# INTERFACE.net
KiCad netlist of a schematic drawn in Altium Designer
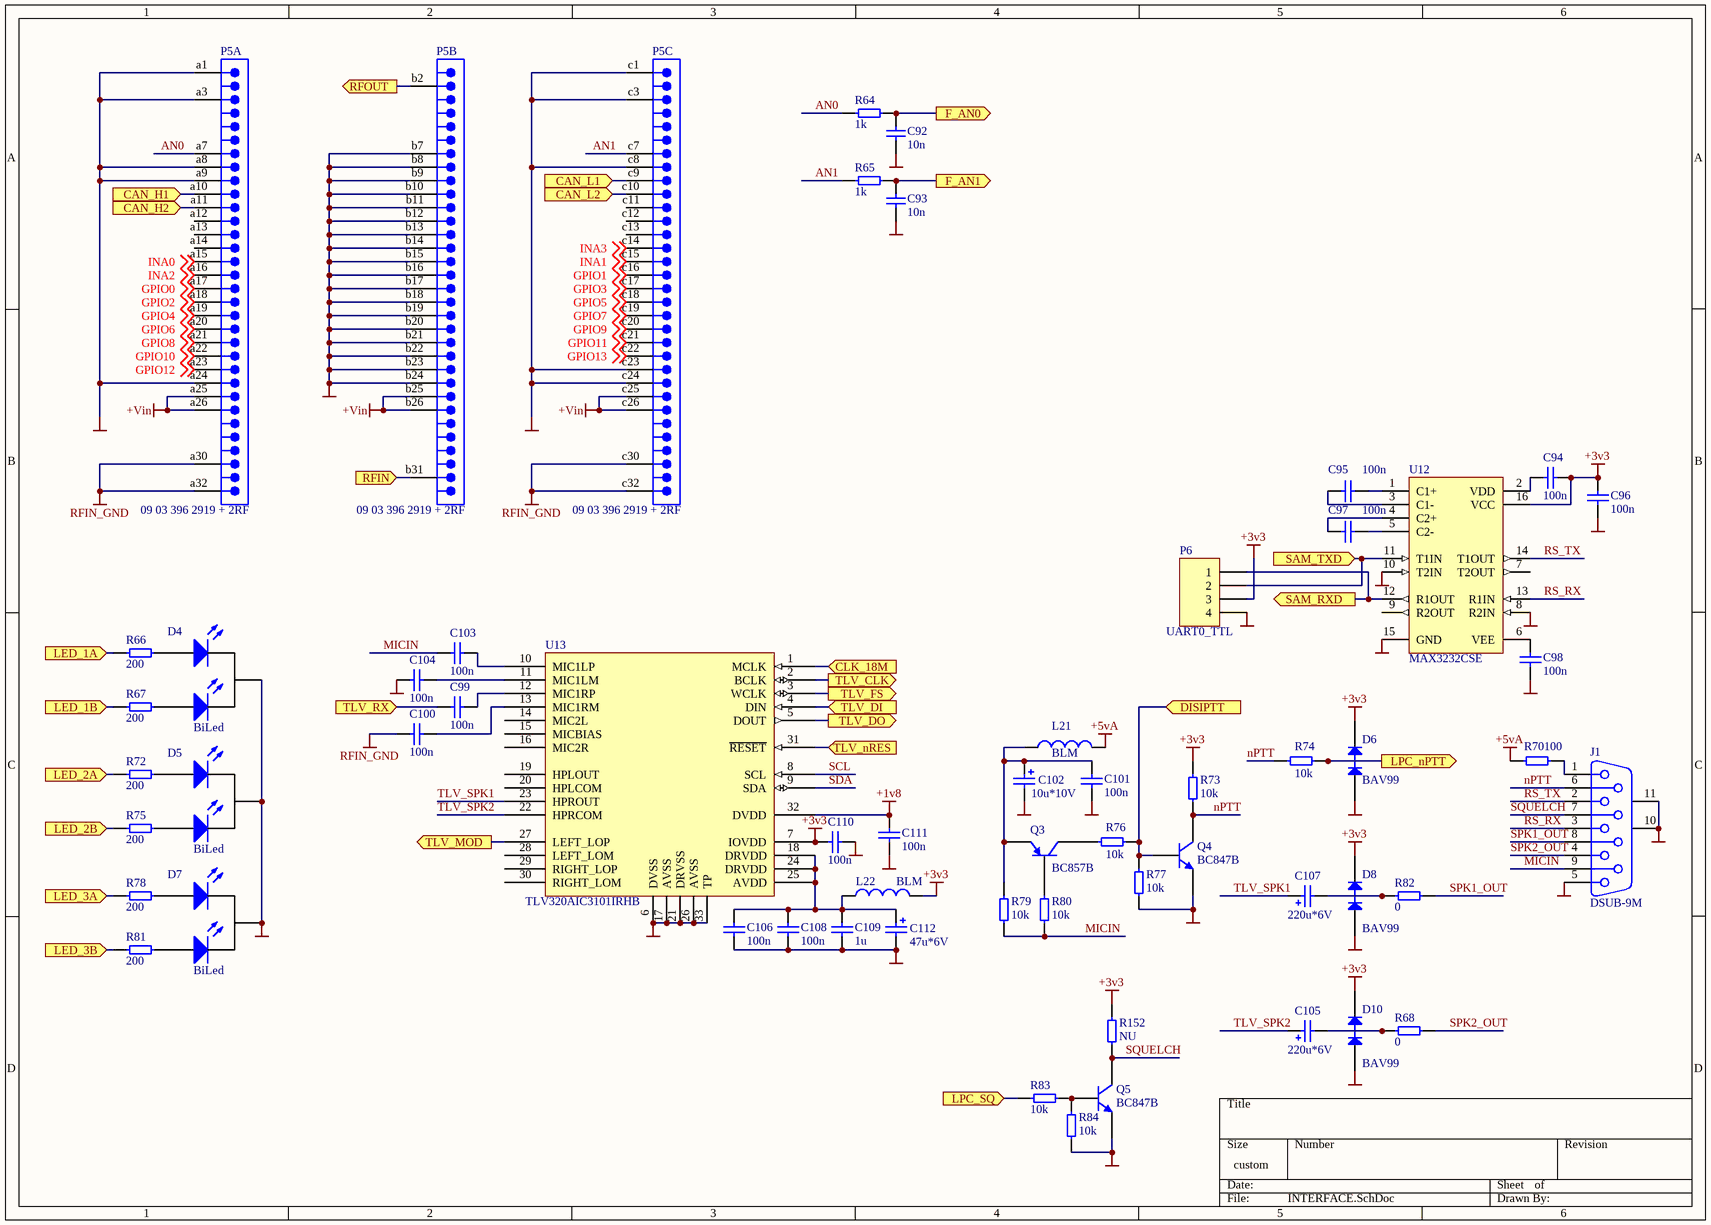
[diagram p0: INTERFACE.SchDoc]

(export (version "E")
  (design (tool "Eeschema 10.0.6"))
  (components
    (comp (ref "C92")
      (value "10n")
      (footprint "CAPC1608L")
      (description "Capacitor")
      (fields (field (name "PUBLISHER") "Altium Limited"))
      (libsource (lib "") (part "Cap_1"))
    )
    (comp (ref "C93")
      (value "10n")
      (footprint "CAPC1608L")
      (description "Capacitor")
      (fields (field (name "PUBLISHER") "Altium Limited"))
      (libsource (lib "") (part "Cap_1"))
    )
    (comp (ref "C94")
      (value "100n")
      (footprint "CAPC1608N")
      (description "Capacitor")
      (fields (field (name "PUBLISHER") "Altium Limited"))
      (libsource (lib "Sch components") (part "Cap"))
    )
    (comp (ref "C95")
      (value "100n")
      (footprint "CAPC1608N")
      (description "Capacitor")
      (fields (field (name "PUBLISHER") "Altium Limited"))
      (libsource (lib "Sch components") (part "Cap"))
    )
    (comp (ref "C96")
      (value "100n")
      (footprint "CAPC1608N")
      (description "Capacitor")
      (fields (field (name "PUBLISHER") "Altium Limited"))
      (libsource (lib "Sch components") (part "Cap"))
    )
    (comp (ref "C97")
      (value "100n")
      (footprint "CAPC1608N")
      (description "Capacitor")
      (fields (field (name "PUBLISHER") "Altium Limited"))
      (libsource (lib "Sch components") (part "Cap"))
    )
    (comp (ref "C98")
      (value "100n")
      (footprint "CAPC1608N")
      (description "Capacitor")
      (fields (field (name "PUBLISHER") "Altium Limited"))
      (libsource (lib "Sch components") (part "Cap"))
    )
    (comp (ref "C99")
      (value "100n")
      (footprint "CAPC1608N")
      (description "Capacitor")
      (fields (field (name "PUBLISHER") "Altium Limited"))
      (libsource (lib "Sch components") (part "Cap"))
    )
    (comp (ref "C100")
      (value "100n")
      (footprint "CAPC1608N")
      (description "Capacitor")
      (fields (field (name "PUBLISHER") "Altium Limited"))
      (libsource (lib "Sch components") (part "Cap"))
    )
    (comp (ref "C101")
      (value "100n")
      (footprint "CAPC1608N")
      (description "Capacitor")
      (fields (field (name "PUBLISHER") "Altium Limited"))
      (libsource (lib "Sch components") (part "Cap"))
    )
    (comp (ref "C102")
      (value "10u*10V")
      (footprint "Case_A")
      (description "Polarized Capacitor (Surface Mount)")
      (fields (field (name "PUBLISHER") "Altium Limited"))
      (libsource (lib "Sch components") (part "Cap Pol"))
    )
    (comp (ref "C103")
      (value "100n")
      (footprint "CAPC1608N")
      (description "Capacitor")
      (fields (field (name "PUBLISHER") "Altium Limited"))
      (libsource (lib "Sch components") (part "Cap"))
    )
    (comp (ref "C104")
      (value "100n")
      (footprint "CAPC1608N")
      (description "Capacitor")
      (fields (field (name "PUBLISHER") "Altium Limited"))
      (libsource (lib "Sch components") (part "Cap"))
    )
    (comp (ref "C105")
      (value "220u*6V")
      (footprint "Case_C")
      (description "Polarized Capacitor (Surface Mount)")
      (fields (field (name "PUBLISHER") "Altium Limited"))
      (libsource (lib "Sch components") (part "Cap Pol"))
    )
    (comp (ref "C106")
      (value "100n")
      (footprint "CAPC1608N")
      (description "Capacitor")
      (fields (field (name "PUBLISHER") "Altium Limited"))
      (libsource (lib "Sch components") (part "Cap"))
    )
    (comp (ref "C107")
      (value "220u*6V")
      (footprint "Case_C")
      (description "Polarized Capacitor (Surface Mount)")
      (fields (field (name "PUBLISHER") "Altium Limited"))
      (libsource (lib "Sch components") (part "Cap Pol"))
    )
    (comp (ref "C108")
      (value "100n")
      (footprint "CAPC1608N")
      (description "Capacitor")
      (fields (field (name "PUBLISHER") "Altium Limited"))
      (libsource (lib "Sch components") (part "Cap"))
    )
    (comp (ref "C109")
      (value "1u")
      (footprint "CAPC2012N")
      (description "Capacitor")
      (fields (field (name "PUBLISHER") "Altium Limited"))
      (libsource (lib "Sch components") (part "Cap"))
    )
    (comp (ref "C110")
      (value "100n")
      (footprint "CAPC1608N")
      (description "Capacitor")
      (fields (field (name "PUBLISHER") "Altium Limited"))
      (libsource (lib "Sch components") (part "Cap"))
    )
    (comp (ref "C111")
      (value "100n")
      (footprint "CAPC1608N")
      (description "Capacitor")
      (fields (field (name "PUBLISHER") "Altium Limited"))
      (libsource (lib "Sch components") (part "Cap"))
    )
    (comp (ref "C112")
      (value "47u*6V")
      (footprint "Case_A")
      (description "Polarized Capacitor (Surface Mount)")
      (fields (field (name "PUBLISHER") "Altium Limited"))
      (libsource (lib "Sch components") (part "Cap Pol"))
    )
    (comp (ref "D4") (value "BiLed") (footprint "BLED-1") (libsource (lib "MyLibrary") (part "BiLed")))
    (comp (ref "D5") (value "BiLed") (footprint "BLED-1") (libsource (lib "MyLibrary") (part "BiLed")))
    (comp (ref "D6")
      (value "BAV99")
      (footprint "SOT-23")
      (description "Silicon Switching Diode Array for High-Speed Switching")
      (fields (field (name "PUBLISHER") "Altium Limited"))
      (libsource (lib "Sch components") (part "BAV99"))
    )
    (comp (ref "D7") (value "BiLed") (footprint "BLED-1") (libsource (lib "MyLibrary") (part "BiLed")))
    (comp (ref "D8")
      (value "BAV99")
      (footprint "SOT-23")
      (description "Silicon Switching Diode Array for High-Speed Switching")
      (fields (field (name "PUBLISHER") "Altium Limited"))
      (libsource (lib "Sch components") (part "BAV99"))
    )
    (comp (ref "D10")
      (value "BAV99")
      (footprint "SOT-23")
      (description "Silicon Switching Diode Array for High-Speed Switching")
      (fields (field (name "PUBLISHER") "Altium Limited"))
      (libsource (lib "Sch components") (part "BAV99"))
    )
    (comp (ref "J1")
      (value "DSUB-9M")
      (footprint "DSUB1.385-2H9")
      (description "Receptacle Assembly, 9 Position, Right Angle")
      (fields (field (name "PUBLISHER") "Altium Limited"))
      (libsource (lib "Miscellaneous Connectors") (part "D Connector 9"))
    )
    (comp (ref "L21")
      (value "BLM")
      (footprint "INDC2012L")
      (libsource (lib "Sch Components") (part "INDUCTOR"))
    )
    (comp (ref "L22") (value "BLM") (footprint "INDC2012L") (libsource (lib "") (part "INDUCTOR_1")))
    (comp (ref "P5")
      (value "09 03 396 2919 + 2RF")
      (footprint "0903396x919")
      (fields (field (name "PUBLISHER") "Altium Limited"))
      (libsource (lib "MyWLib") (part "09 03 396 2919"))
    )
    (comp (ref "P6")
      (value "UART0_TTL")
      (footprint "HDR1X4")
      (description "Header, 4-Pin")
      (fields (field (name "PUBLISHER") "Altium Limited"))
      (libsource (lib "Miscellaneous Connectors") (part "Header 4"))
    )
    (comp (ref "Q3")
      (value "BC857B")
      (footprint "SOT23_N")
      (description "PNP General-purpose Transistor")
      (fields (field (name "PUBLISHER") "Altium Limited"))
      (libsource (lib "Philips Discrete BJT - Low Power") (part "BC857B"))
    )
    (comp (ref "Q4")
      (value "BC847B")
      (footprint "SOT23_N")
      (description "NPN General-purpose Transistor")
      (fields (field (name "PUBLISHER") "Altium Limited"))
      (libsource (lib "Philips Discrete BJT - Low Power") (part "BC847B"))
    )
    (comp (ref "Q5")
      (value "BC847B")
      (footprint "SOT23_N")
      (description "NPN General-purpose Transistor")
      (fields (field (name "PUBLISHER") "Altium Limited"))
      (libsource (lib "Philips Discrete BJT - Low Power") (part "BC847B"))
    )
    (comp (ref "R64")
      (value "1k")
      (footprint "RESC1608L")
      (description "Resistor")
      (fields (field (name "PUBLISHER") "Altium Limited"))
      (libsource (lib "Sch components") (part "Res"))
    )
    (comp (ref "R65")
      (value "1k")
      (footprint "RESC1608L")
      (description "Resistor")
      (fields (field (name "PUBLISHER") "Altium Limited"))
      (libsource (lib "Sch components") (part "Res"))
    )
    (comp (ref "R66")
      (value "200")
      (footprint "RESC1608L")
      (description "Resistor")
      (fields (field (name "PUBLISHER") "Altium Limited"))
      (libsource (lib "Sch components") (part "Res"))
    )
    (comp (ref "R67")
      (value "200")
      (footprint "RESC1608L")
      (description "Resistor")
      (fields (field (name "PUBLISHER") "Altium Limited"))
      (libsource (lib "Sch components") (part "Res"))
    )
    (comp (ref "R68")
      (value "0")
      (footprint "RESC2012L")
      (description "Resistor")
      (fields (field (name "PUBLISHER") "Altium Limited"))
      (libsource (lib "Sch components") (part "Res"))
    )
    (comp (ref "R70")
      (value "100")
      (footprint "RESC2012L")
      (description "Resistor")
      (fields (field (name "PUBLISHER") "Altium Limited"))
      (libsource (lib "Sch components") (part "Res"))
    )
    (comp (ref "R72")
      (value "200")
      (footprint "RESC1608L")
      (description "Resistor")
      (fields (field (name "PUBLISHER") "Altium Limited"))
      (libsource (lib "Sch components") (part "Res"))
    )
    (comp (ref "R73")
      (value "10k")
      (footprint "RESC1608L")
      (description "Resistor")
      (fields (field (name "PUBLISHER") "Altium Limited"))
      (libsource (lib "Sch components") (part "Res"))
    )
    (comp (ref "R74")
      (value "10k")
      (footprint "RESC1608L")
      (description "Resistor")
      (fields (field (name "PUBLISHER") "Altium Limited"))
      (libsource (lib "Sch components") (part "Res"))
    )
    (comp (ref "R75")
      (value "200")
      (footprint "RESC1608L")
      (description "Resistor")
      (fields (field (name "PUBLISHER") "Altium Limited"))
      (libsource (lib "Sch components") (part "Res"))
    )
    (comp (ref "R76")
      (value "10k")
      (footprint "RESC1608L")
      (description "Resistor")
      (fields (field (name "PUBLISHER") "Altium Limited"))
      (libsource (lib "Sch components") (part "Res"))
    )
    (comp (ref "R77")
      (value "10k")
      (footprint "RESC1608L")
      (description "Resistor")
      (fields (field (name "PUBLISHER") "Altium Limited"))
      (libsource (lib "Sch components") (part "Res"))
    )
    (comp (ref "R78")
      (value "200")
      (footprint "RESC1608L")
      (description "Resistor")
      (fields (field (name "PUBLISHER") "Altium Limited"))
      (libsource (lib "Sch components") (part "Res"))
    )
    (comp (ref "R79")
      (value "10k")
      (footprint "RESC1608L")
      (description "Resistor")
      (fields (field (name "PUBLISHER") "Altium Limited"))
      (libsource (lib "Sch components") (part "Res"))
    )
    (comp (ref "R80")
      (value "10k")
      (footprint "RESC1608L")
      (description "Resistor")
      (fields (field (name "PUBLISHER") "Altium Limited"))
      (libsource (lib "Sch components") (part "Res"))
    )
    (comp (ref "R81")
      (value "200")
      (footprint "RESC1608L")
      (description "Resistor")
      (fields (field (name "PUBLISHER") "Altium Limited"))
      (libsource (lib "Sch components") (part "Res"))
    )
    (comp (ref "R82")
      (value "0")
      (footprint "RESC2012L")
      (description "Resistor")
      (fields (field (name "PUBLISHER") "Altium Limited"))
      (libsource (lib "Sch components") (part "Res"))
    )
    (comp (ref "R83")
      (value "10k")
      (footprint "RESC1608L")
      (description "Resistor")
      (fields (field (name "PUBLISHER") "Altium Limited"))
      (libsource (lib "Sch components") (part "Res"))
    )
    (comp (ref "R84")
      (value "10k")
      (footprint "RESC1608L")
      (description "Resistor")
      (fields (field (name "PUBLISHER") "Altium Limited"))
      (libsource (lib "Sch components") (part "Res"))
    )
    (comp (ref "R152")
      (value "NU")
      (footprint "RESC1608L")
      (description "Resistor")
      (fields (field (name "PUBLISHER") "Altium Limited"))
      (libsource (lib "Sch components") (part "Res"))
    )
    (comp (ref "U12")
      (value "MAX3232CSE")
      (footprint "NSO16_N")
      (description "+5V Powered, Multi-Channel RS-232 Driver/Receiver")
      (fields (field (name "PUBLISHER") "Altium Limited"))
      (libsource (lib "Maxim Communication Transceiver") (part "MAX232CSE"))
    )
    (comp (ref "U13")
      (value "TLV320AIC3101IRHB")
      (footprint "Pcb components:QFN50P500X500-32W6N")
      (description "Low-power stereo codec")
      (libsource (lib "Sch components") (part "TLV320AIC3101IRHB"))
    )
  )
  (nets
    (net (code "1") (name "+1v8") (class "Default")
      (node (ref "C111") (pin "2") (pinfunction "2_2") (pintype "passive"))
      (node (ref "U13") (pin "32") (pinfunction "DVDD_32") (pintype "power_in"))
    )
    (net (code "2") (name "+3v3") (class "Default")
      (node (ref "C110") (pin "2") (pinfunction "2_2") (pintype "passive"))
      (node (ref "C94") (pin "1") (pinfunction "1_1") (pintype "passive"))
      (node (ref "C96") (pin "2") (pinfunction "2_2") (pintype "passive"))
      (node (ref "D10") (pin "2") (pinfunction "K_2") (pintype "passive"))
      (node (ref "D6") (pin "2") (pinfunction "K_2") (pintype "passive"))
      (node (ref "D8") (pin "2") (pinfunction "K_2") (pintype "passive"))
      (node (ref "L22") (pin "1") (pinfunction "1_1") (pintype "passive"))
      (node (ref "P6") (pin "3") (pinfunction "3_3") (pintype "passive"))
      (node (ref "R152") (pin "2") (pinfunction "2_2") (pintype "passive"))
      (node (ref "R73") (pin "2") (pinfunction "2_2") (pintype "passive"))
      (node (ref "U12") (pin "16") (pinfunction "VCC_16") (pintype "power_in"))
      (node (ref "U13") (pin "7") (pinfunction "IOVDD_7") (pintype "power_in"))
    )
    (net (code "3") (name "+5vA") (class "Default")
      (node (ref "L21") (pin "2") (pinfunction "2_2") (pintype "passive"))
      (node (ref "R70") (pin "1") (pinfunction "1_1") (pintype "passive"))
    )
    (net (code "4") (name "+Vin") (class "Default")
      (node (ref "P5") (pin "a25") (pinfunction "a25_a25") (pintype "passive"))
      (node (ref "P5") (pin "a26") (pinfunction "a26_a26") (pintype "passive"))
      (node (ref "P5") (pin "b25") (pinfunction "b25_b25") (pintype "passive"))
      (node (ref "P5") (pin "b26") (pinfunction "b26_b26") (pintype "passive"))
      (node (ref "P5") (pin "c25") (pinfunction "c25_c25") (pintype "passive"))
      (node (ref "P5") (pin "c26") (pinfunction "c26_c26") (pintype "passive"))
    )
    (net (code "5") (name "/AN0") (class "Default")
      (node (ref "P5") (pin "a7") (pinfunction "a7_a7") (pintype "passive"))
      (node (ref "R64") (pin "1") (pinfunction "1_1") (pintype "passive"))
    )
    (net (code "6") (name "/AN1") (class "Default")
      (node (ref "P5") (pin "c7") (pinfunction "c7_c7") (pintype "passive"))
      (node (ref "R65") (pin "1") (pinfunction "1_1") (pintype "passive"))
    )
    (net (code "7") (name "/CAN_H1") (class "Default")
      (node (ref "P5") (pin "a10") (pinfunction "a10_a10") (pintype "passive"))
    )
    (net (code "8") (name "/CAN_H2") (class "Default")
      (node (ref "P5") (pin "a11") (pinfunction "a11_a11") (pintype "passive"))
    )
    (net (code "9") (name "/CAN_L1") (class "Default")
      (node (ref "P5") (pin "c9") (pinfunction "c9_c9") (pintype "passive"))
    )
    (net (code "10") (name "/CAN_L2") (class "Default")
      (node (ref "P5") (pin "c10") (pinfunction "c10_c10") (pintype "passive"))
    )
    (net (code "11") (name "/CLK_18M") (class "Default")
      (node (ref "U13") (pin "1") (pinfunction "MCLK_1") (pintype "input"))
    )
    (net (code "12") (name "/DISIPTT") (class "Default")
      (node (ref "Q4") (pin "1") (pinfunction "B_1") (pintype "passive"))
      (node (ref "R76") (pin "1") (pinfunction "1_1") (pintype "passive"))
      (node (ref "R77") (pin "2") (pinfunction "2_2") (pintype "passive"))
    )
    (net (code "13") (name "/F_AN0") (class "Default")
      (node (ref "C92") (pin "2") (pinfunction "2_2") (pintype "passive"))
      (node (ref "R64") (pin "2") (pinfunction "2_2") (pintype "passive"))
    )
    (net (code "14") (name "/F_AN1") (class "Default")
      (node (ref "C93") (pin "2") (pinfunction "2_2") (pintype "passive"))
      (node (ref "R65") (pin "2") (pinfunction "2_2") (pintype "passive"))
    )
    (net (code "15") (name "/LED_1A") (class "Default")
      (node (ref "R66") (pin "2") (pinfunction "2_2") (pintype "passive"))
    )
    (net (code "16") (name "/LED_1B") (class "Default")
      (node (ref "R67") (pin "2") (pinfunction "2_2") (pintype "passive"))
    )
    (net (code "17") (name "/LED_2A") (class "Default")
      (node (ref "R72") (pin "2") (pinfunction "2_2") (pintype "passive"))
    )
    (net (code "18") (name "/LED_2B") (class "Default")
      (node (ref "R75") (pin "2") (pinfunction "2_2") (pintype "passive"))
    )
    (net (code "19") (name "/LED_3A") (class "Default")
      (node (ref "R78") (pin "2") (pinfunction "2_2") (pintype "passive"))
    )
    (net (code "20") (name "/LED_3B") (class "Default")
      (node (ref "R81") (pin "2") (pinfunction "2_2") (pintype "passive"))
    )
    (net (code "21") (name "/LPC_SQ") (class "Default")
      (node (ref "R83") (pin "1") (pinfunction "1_1") (pintype "passive"))
    )
    (net (code "22") (name "/LPC_nPTT") (class "Default")
      (node (ref "D6") (pin "3") (pinfunction "C_3") (pintype "passive"))
      (node (ref "R74") (pin "1") (pinfunction "1_1") (pintype "passive"))
    )
    (net (code "23") (name "/MICIN") (class "Default")
      (node (ref "C103") (pin "1") (pinfunction "1_1") (pintype "passive"))
      (node (ref "J1") (pin "9") (pinfunction "9_9") (pintype "passive"))
      (node (ref "R79") (pin "1") (pinfunction "1_1") (pintype "passive"))
      (node (ref "R80") (pin "1") (pinfunction "1_1") (pintype "passive"))
    )
    (net (code "24") (name "/RFIN") (class "Default")
      (node (ref "P5") (pin "b31") (pinfunction "b31_b31") (pintype "passive"))
    )
    (net (code "25") (name "/RFOUT") (class "Default")
      (node (ref "P5") (pin "b2") (pinfunction "b2_b2") (pintype "passive"))
    )
    (net (code "26") (name "/RS_RX") (class "Default")
      (node (ref "J1") (pin "3") (pinfunction "3_3") (pintype "passive"))
      (node (ref "U12") (pin "13") (pinfunction "R1IN_13") (pintype "input"))
    )
    (net (code "27") (name "/RS_TX") (class "Default")
      (node (ref "J1") (pin "2") (pinfunction "2_2") (pintype "passive"))
      (node (ref "U12") (pin "14") (pinfunction "T1OUT_14") (pintype "output"))
    )
    (net (code "28") (name "/SAM_RXD") (class "Default")
      (node (ref "P6") (pin "1") (pinfunction "1_1") (pintype "passive"))
      (node (ref "U12") (pin "12") (pinfunction "R1OUT_12") (pintype "output"))
    )
    (net (code "29") (name "/SAM_TXD") (class "Default")
      (node (ref "P6") (pin "2") (pinfunction "2_2") (pintype "passive"))
      (node (ref "U12") (pin "11") (pinfunction "T1IN_11") (pintype "input"))
    )
    (net (code "30") (name "/SCL") (class "Default")
      (node (ref "U13") (pin "8") (pinfunction "SCL_8") (pintype "input"))
    )
    (net (code "31") (name "/SDA") (class "Default")
      (node (ref "U13") (pin "9") (pinfunction "SDA_9") (pintype "bidirectional"))
    )
    (net (code "32") (name "/SPK1_OUT") (class "Default")
      (node (ref "J1") (pin "8") (pinfunction "8_8") (pintype "passive"))
      (node (ref "R82") (pin "2") (pinfunction "2_2") (pintype "passive"))
    )
    (net (code "33") (name "/SPK2_OUT") (class "Default")
      (node (ref "J1") (pin "4") (pinfunction "4_4") (pintype "passive"))
      (node (ref "R68") (pin "2") (pinfunction "2_2") (pintype "passive"))
    )
    (net (code "34") (name "/SQUELCH") (class "Default")
      (node (ref "J1") (pin "7") (pinfunction "7_7") (pintype "passive"))
      (node (ref "Q5") (pin "3") (pinfunction "C_3") (pintype "passive"))
      (node (ref "R152") (pin "1") (pinfunction "1_1") (pintype "passive"))
    )
    (net (code "35") (name "/TLV_CLK") (class "Default")
      (node (ref "U13") (pin "2") (pinfunction "BCLK_2") (pintype "bidirectional"))
    )
    (net (code "36") (name "/TLV_DI") (class "Default")
      (node (ref "U13") (pin "4") (pinfunction "DIN_4") (pintype "input"))
    )
    (net (code "37") (name "/TLV_DO") (class "Default")
      (node (ref "U13") (pin "5") (pinfunction "DOUT_5") (pintype "output"))
    )
    (net (code "38") (name "/TLV_FS") (class "Default")
      (node (ref "U13") (pin "3") (pinfunction "WCLK_3") (pintype "bidirectional"))
    )
    (net (code "39") (name "/TLV_MOD") (class "Default")
      (node (ref "U13") (pin "27") (pinfunction "LEFT_LOP_27") (pintype "passive"))
    )
    (net (code "40") (name "/TLV_RX") (class "Default")
      (node (ref "C99") (pin "1") (pinfunction "1_1") (pintype "passive"))
    )
    (net (code "41") (name "/TLV_SPK1") (class "Default")
      (node (ref "C107") (pin "1") (pinfunction "1_1") (pintype "passive"))
      (node (ref "U13") (pin "23") (pinfunction "HPROUT_23") (pintype "passive"))
    )
    (net (code "42") (name "/TLV_SPK2") (class "Default")
      (node (ref "C105") (pin "1") (pinfunction "1_1") (pintype "passive"))
      (node (ref "U13") (pin "22") (pinfunction "HPRCOM_22") (pintype "passive"))
    )
    (net (code "43") (name "/TLV_nRES") (class "Default")
      (node (ref "U13") (pin "31") (pinfunction "~{RESET}_31") (pintype "input"))
    )
    (net (code "44") (name "/nPTT") (class "Default")
      (node (ref "J1") (pin "6") (pinfunction "6_6") (pintype "passive"))
      (node (ref "Q4") (pin "3") (pinfunction "C_3") (pintype "passive"))
      (node (ref "R73") (pin "1") (pinfunction "1_1") (pintype "passive"))
      (node (ref "R74") (pin "2") (pinfunction "2_2") (pintype "passive"))
    )
    (net (code "45") (name "GND") (class "Default")
      (node (ref "C101") (pin "2") (pinfunction "2_2") (pintype "passive"))
      (node (ref "C102") (pin "2") (pinfunction "2_2") (pintype "passive"))
      (node (ref "C104") (pin "2") (pinfunction "2_2") (pintype "passive"))
      (node (ref "C106") (pin "1") (pinfunction "1_1") (pintype "passive"))
      (node (ref "C108") (pin "1") (pinfunction "1_1") (pintype "passive"))
      (node (ref "C109") (pin "1") (pinfunction "1_1") (pintype "passive"))
      (node (ref "C110") (pin "1") (pinfunction "1_1") (pintype "passive"))
      (node (ref "C111") (pin "1") (pinfunction "1_1") (pintype "passive"))
      (node (ref "C112") (pin "2") (pinfunction "2_2") (pintype "passive"))
      (node (ref "C92") (pin "1") (pinfunction "1_1") (pintype "passive"))
      (node (ref "C93") (pin "1") (pinfunction "1_1") (pintype "passive"))
      (node (ref "C96") (pin "1") (pinfunction "1_1") (pintype "passive"))
      (node (ref "C98") (pin "1") (pinfunction "1_1") (pintype "passive"))
      (node (ref "D10") (pin "1") (pinfunction "A_1") (pintype "passive"))
      (node (ref "D4") (pin "2") (pinfunction "2_2") (pintype "passive"))
      (node (ref "D5") (pin "2") (pinfunction "2_2") (pintype "passive"))
      (node (ref "D6") (pin "1") (pinfunction "A_1") (pintype "passive"))
      (node (ref "D7") (pin "2") (pinfunction "2_2") (pintype "passive"))
      (node (ref "D8") (pin "1") (pinfunction "A_1") (pintype "passive"))
      (node (ref "J1") (pin "10") (pinfunction "MH1_10") (pintype "passive"))
      (node (ref "J1") (pin "11") (pinfunction "MH2_11") (pintype "passive"))
      (node (ref "J1") (pin "5") (pinfunction "5_5") (pintype "passive"))
      (node (ref "P5") (pin "a1") (pinfunction "a1_a1") (pintype "passive"))
      (node (ref "P5") (pin "a24") (pinfunction "a24_a24") (pintype "passive"))
      (node (ref "P5") (pin "a3") (pinfunction "a3_a3") (pintype "passive"))
      (node (ref "P5") (pin "a8") (pinfunction "a8_a8") (pintype "passive"))
      (node (ref "P5") (pin "a9") (pinfunction "a9_a9") (pintype "passive"))
      (node (ref "P5") (pin "b10") (pinfunction "b10_b10") (pintype "passive"))
      (node (ref "P5") (pin "b11") (pinfunction "b11_b11") (pintype "passive"))
      (node (ref "P5") (pin "b12") (pinfunction "b12_b12") (pintype "passive"))
      (node (ref "P5") (pin "b13") (pinfunction "b13_b13") (pintype "passive"))
      (node (ref "P5") (pin "b14") (pinfunction "b14_b14") (pintype "passive"))
      (node (ref "P5") (pin "b15") (pinfunction "b15_b15") (pintype "passive"))
      (node (ref "P5") (pin "b16") (pinfunction "b16_b16") (pintype "passive"))
      (node (ref "P5") (pin "b17") (pinfunction "b17_b17") (pintype "passive"))
      (node (ref "P5") (pin "b18") (pinfunction "b18_b18") (pintype "passive"))
      (node (ref "P5") (pin "b19") (pinfunction "b19_b19") (pintype "passive"))
      (node (ref "P5") (pin "b20") (pinfunction "b20_b20") (pintype "passive"))
      (node (ref "P5") (pin "b21") (pinfunction "b21_b21") (pintype "passive"))
      (node (ref "P5") (pin "b22") (pinfunction "b22_b22") (pintype "passive"))
      (node (ref "P5") (pin "b23") (pinfunction "b23_b23") (pintype "passive"))
      (node (ref "P5") (pin "b24") (pinfunction "b24_b24") (pintype "passive"))
      (node (ref "P5") (pin "b7") (pinfunction "b7_b7") (pintype "passive"))
      (node (ref "P5") (pin "b8") (pinfunction "b8_b8") (pintype "passive"))
      (node (ref "P5") (pin "b9") (pinfunction "b9_b9") (pintype "passive"))
      (node (ref "P5") (pin "c1") (pinfunction "c1_c1") (pintype "passive"))
      (node (ref "P5") (pin "c23") (pinfunction "c23_c23") (pintype "passive"))
      (node (ref "P5") (pin "c24") (pinfunction "c24_c24") (pintype "passive"))
      (node (ref "P5") (pin "c3") (pinfunction "c3_c3") (pintype "passive"))
      (node (ref "P5") (pin "c8") (pinfunction "c8_c8") (pintype "passive"))
      (node (ref "P6") (pin "4") (pinfunction "4_4") (pintype "passive"))
      (node (ref "Q4") (pin "2") (pinfunction "E_2") (pintype "passive"))
      (node (ref "Q5") (pin "2") (pinfunction "E_2") (pintype "passive"))
      (node (ref "R77") (pin "1") (pinfunction "1_1") (pintype "passive"))
      (node (ref "R84") (pin "2") (pinfunction "2_2") (pintype "passive"))
      (node (ref "U12") (pin "10") (pinfunction "T2IN_10") (pintype "input"))
      (node (ref "U12") (pin "15") (pinfunction "GND_15") (pintype "power_in"))
      (node (ref "U12") (pin "8") (pinfunction "R2IN_8") (pintype "input"))
      (node (ref "U13") (pin "17") (pinfunction "AVSS_17") (pintype "power_in"))
      (node (ref "U13") (pin "21") (pinfunction "DRVSS_21") (pintype "power_in"))
      (node (ref "U13") (pin "26") (pinfunction "AVSS_26") (pintype "power_in"))
      (node (ref "U13") (pin "33") (pinfunction "TP_33") (pintype "power_in"))
      (node (ref "U13") (pin "6") (pinfunction "DVSS_6") (pintype "power_in"))
    )
    (net (code "46") (name "GPIO0") (class "Default")
      (node (ref "P5") (pin "a17") (pinfunction "a17_a17") (pintype "passive"))
    )
    (net (code "47") (name "GPIO1") (class "Default")
      (node (ref "P5") (pin "c16") (pinfunction "c16_c16") (pintype "passive"))
    )
    (net (code "48") (name "GPIO2") (class "Default")
      (node (ref "P5") (pin "a18") (pinfunction "a18_a18") (pintype "passive"))
    )
    (net (code "49") (name "GPIO3") (class "Default")
      (node (ref "P5") (pin "c17") (pinfunction "c17_c17") (pintype "passive"))
    )
    (net (code "50") (name "GPIO4") (class "Default")
      (node (ref "P5") (pin "a19") (pinfunction "a19_a19") (pintype "passive"))
    )
    (net (code "51") (name "GPIO5") (class "Default")
      (node (ref "P5") (pin "c18") (pinfunction "c18_c18") (pintype "passive"))
    )
    (net (code "52") (name "GPIO6") (class "Default")
      (node (ref "P5") (pin "a20") (pinfunction "a20_a20") (pintype "passive"))
    )
    (net (code "53") (name "GPIO7") (class "Default")
      (node (ref "P5") (pin "c19") (pinfunction "c19_c19") (pintype "passive"))
    )
    (net (code "54") (name "GPIO8") (class "Default")
      (node (ref "P5") (pin "a21") (pinfunction "a21_a21") (pintype "passive"))
    )
    (net (code "55") (name "GPIO9") (class "Default")
      (node (ref "P5") (pin "c20") (pinfunction "c20_c20") (pintype "passive"))
    )
    (net (code "56") (name "GPIO10") (class "Default")
      (node (ref "P5") (pin "a22") (pinfunction "a22_a22") (pintype "passive"))
    )
    (net (code "57") (name "GPIO11") (class "Default")
      (node (ref "P5") (pin "c21") (pinfunction "c21_c21") (pintype "passive"))
    )
    (net (code "58") (name "GPIO12") (class "Default")
      (node (ref "P5") (pin "a23") (pinfunction "a23_a23") (pintype "passive"))
    )
    (net (code "59") (name "GPIO13") (class "Default")
      (node (ref "P5") (pin "c22") (pinfunction "c22_c22") (pintype "passive"))
    )
    (net (code "60") (name "INA0") (class "Default")
      (node (ref "P5") (pin "a15") (pinfunction "a15_a15") (pintype "passive"))
    )
    (net (code "61") (name "INA1") (class "Default")
      (node (ref "P5") (pin "c15") (pinfunction "c15_c15") (pintype "passive"))
    )
    (net (code "62") (name "INA2") (class "Default")
      (node (ref "P5") (pin "a16") (pinfunction "a16_a16") (pintype "passive"))
    )
    (net (code "63") (name "INA3") (class "Default")
      (node (ref "P5") (pin "c14") (pinfunction "c14_c14") (pintype "passive"))
    )
    (net (code "64") (name "Net-(D4-Pad1)") (class "Default")
      (node (ref "D4") (pin "1") (pinfunction "1_1") (pintype "passive"))
      (node (ref "R66") (pin "1") (pinfunction "1_1") (pintype "passive"))
    )
    (net (code "65") (name "Net-(D4-Pad3)") (class "Default")
      (node (ref "D4") (pin "3") (pinfunction "3_3") (pintype "passive"))
      (node (ref "R67") (pin "1") (pinfunction "1_1") (pintype "passive"))
    )
    (net (code "66") (name "Net-(D5-Pad1)") (class "Default")
      (node (ref "D5") (pin "1") (pinfunction "1_1") (pintype "passive"))
      (node (ref "R72") (pin "1") (pinfunction "1_1") (pintype "passive"))
    )
    (net (code "67") (name "Net-(D5-Pad3)") (class "Default")
      (node (ref "D5") (pin "3") (pinfunction "3_3") (pintype "passive"))
      (node (ref "R75") (pin "1") (pinfunction "1_1") (pintype "passive"))
    )
    (net (code "68") (name "Net-(D7-Pad1)") (class "Default")
      (node (ref "D7") (pin "1") (pinfunction "1_1") (pintype "passive"))
      (node (ref "R78") (pin "1") (pinfunction "1_1") (pintype "passive"))
    )
    (net (code "69") (name "Net-(D7-Pad3)") (class "Default")
      (node (ref "D7") (pin "3") (pinfunction "3_3") (pintype "passive"))
      (node (ref "R81") (pin "1") (pinfunction "1_1") (pintype "passive"))
    )
    (net (code "70") (name "Net-(D8-C)") (class "Default")
      (node (ref "C107") (pin "2") (pinfunction "2_2") (pintype "passive"))
      (node (ref "D8") (pin "3") (pinfunction "C_3") (pintype "passive"))
      (node (ref "R82") (pin "1") (pinfunction "1_1") (pintype "passive"))
    )
    (net (code "71") (name "Net-(D10-C)") (class "Default")
      (node (ref "C105") (pin "2") (pinfunction "2_2") (pintype "passive"))
      (node (ref "D10") (pin "3") (pinfunction "C_3") (pintype "passive"))
      (node (ref "R68") (pin "1") (pinfunction "1_1") (pintype "passive"))
    )
    (net (code "72") (name "Net-(J1-Pad1)") (class "Default")
      (node (ref "J1") (pin "1") (pinfunction "1_1") (pintype "passive"))
      (node (ref "R70") (pin "2") (pinfunction "2_2") (pintype "passive"))
    )
    (net (code "73") (name "Net-(Q3-B)") (class "Default")
      (node (ref "Q3") (pin "1") (pinfunction "B_1") (pintype "passive"))
      (node (ref "R80") (pin "2") (pinfunction "2_2") (pintype "passive"))
    )
    (net (code "74") (name "Net-(Q3-C)") (class "Default")
      (node (ref "Q3") (pin "3") (pinfunction "C_3") (pintype "passive"))
      (node (ref "R76") (pin "2") (pinfunction "2_2") (pintype "passive"))
    )
    (net (code "75") (name "Net-(Q3-E)") (class "Default")
      (node (ref "C101") (pin "1") (pinfunction "1_1") (pintype "passive"))
      (node (ref "C102") (pin "1") (pinfunction "1_1") (pintype "passive"))
      (node (ref "L21") (pin "1") (pinfunction "1_1") (pintype "passive"))
      (node (ref "Q3") (pin "2") (pinfunction "E_2") (pintype "passive"))
      (node (ref "R79") (pin "2") (pinfunction "2_2") (pintype "passive"))
    )
    (net (code "76") (name "Net-(Q5-B)") (class "Default")
      (node (ref "Q5") (pin "1") (pinfunction "B_1") (pintype "passive"))
      (node (ref "R83") (pin "2") (pinfunction "2_2") (pintype "passive"))
      (node (ref "R84") (pin "1") (pinfunction "1_1") (pintype "passive"))
    )
    (net (code "77") (name "Net-(U12-C1+)") (class "Default")
      (node (ref "C95") (pin "2") (pinfunction "2_2") (pintype "passive"))
      (node (ref "U12") (pin "1") (pinfunction "C1+_1") (pintype "passive"))
    )
    (net (code "78") (name "Net-(U12-C1-)") (class "Default")
      (node (ref "C95") (pin "1") (pinfunction "1_1") (pintype "passive"))
      (node (ref "U12") (pin "3") (pinfunction "C1-_3") (pintype "passive"))
    )
    (net (code "79") (name "Net-(U12-C2+)") (class "Default")
      (node (ref "C97") (pin "1") (pinfunction "1_1") (pintype "passive"))
      (node (ref "U12") (pin "4") (pinfunction "C2+_4") (pintype "passive"))
    )
    (net (code "80") (name "Net-(U12-C2-)") (class "Default")
      (node (ref "C97") (pin "2") (pinfunction "2_2") (pintype "passive"))
      (node (ref "U12") (pin "5") (pinfunction "C2-_5") (pintype "passive"))
    )
    (net (code "81") (name "Net-(U12-VDD)") (class "Default")
      (node (ref "C94") (pin "2") (pinfunction "2_2") (pintype "passive"))
      (node (ref "U12") (pin "2") (pinfunction "VDD_2") (pintype "power_in"))
    )
    (net (code "82") (name "Net-(U12-VEE)") (class "Default")
      (node (ref "C98") (pin "2") (pinfunction "2_2") (pintype "passive"))
      (node (ref "U12") (pin "6") (pinfunction "VEE_6") (pintype "power_in"))
    )
    (net (code "83") (name "Net-(U13-AVDD)") (class "Default")
      (node (ref "C106") (pin "2") (pinfunction "2_2") (pintype "passive"))
      (node (ref "C108") (pin "2") (pinfunction "2_2") (pintype "passive"))
      (node (ref "C109") (pin "2") (pinfunction "2_2") (pintype "passive"))
      (node (ref "C112") (pin "1") (pinfunction "1_1") (pintype "passive"))
      (node (ref "L22") (pin "2") (pinfunction "2_2") (pintype "passive"))
      (node (ref "U13") (pin "18") (pinfunction "DRVDD_18") (pintype "power_in"))
      (node (ref "U13") (pin "24") (pinfunction "DRVDD_24") (pintype "power_in"))
      (node (ref "U13") (pin "25") (pinfunction "AVDD_25") (pintype "power_in"))
    )
    (net (code "84") (name "Net-(U13-MIC1LM)") (class "Default")
      (node (ref "C104") (pin "1") (pinfunction "1_1") (pintype "passive"))
      (node (ref "U13") (pin "11") (pinfunction "MIC1LM_11") (pintype "passive"))
    )
    (net (code "85") (name "Net-(U13-MIC1LP)") (class "Default")
      (node (ref "C103") (pin "2") (pinfunction "2_2") (pintype "passive"))
      (node (ref "U13") (pin "10") (pinfunction "MIC1LP_10") (pintype "passive"))
    )
    (net (code "86") (name "Net-(U13-MIC1RM)") (class "Default")
      (node (ref "C100") (pin "1") (pinfunction "1_1") (pintype "passive"))
      (node (ref "U13") (pin "13") (pinfunction "MIC1RM_13") (pintype "passive"))
    )
    (net (code "87") (name "Net-(U13-MIC1RP)") (class "Default")
      (node (ref "C99") (pin "2") (pinfunction "2_2") (pintype "passive"))
      (node (ref "U13") (pin "12") (pinfunction "MIC1RP_12") (pintype "passive"))
    )
    (net (code "88") (name "RFIN_GND") (class "Default")
      (node (ref "C100") (pin "2") (pinfunction "2_2") (pintype "passive"))
      (node (ref "P5") (pin "a30") (pinfunction "a30_a30") (pintype "passive"))
      (node (ref "P5") (pin "a32") (pinfunction "a32_a32") (pintype "passive"))
      (node (ref "P5") (pin "c30") (pinfunction "c30_c30") (pintype "passive"))
      (node (ref "P5") (pin "c32") (pinfunction "c32_c32") (pintype "passive"))
    )
    (net (code "89") (name "unconnected-(P5-Pada12)") (class "Default")
      (node (ref "P5") (pin "a12") (pinfunction "a12_a12") (pintype "passive"))
    )
    (net (code "90") (name "unconnected-(P5-Pada13)") (class "Default")
      (node (ref "P5") (pin "a13") (pinfunction "a13_a13") (pintype "passive"))
    )
    (net (code "91") (name "unconnected-(P5-Pada14)") (class "Default")
      (node (ref "P5") (pin "a14") (pinfunction "a14_a14") (pintype "passive"))
    )
    (net (code "92") (name "unconnected-(P5-Padc11)") (class "Default")
      (node (ref "P5") (pin "c11") (pinfunction "c11_c11") (pintype "passive"))
    )
    (net (code "93") (name "unconnected-(P5-Padc12)") (class "Default")
      (node (ref "P5") (pin "c12") (pinfunction "c12_c12") (pintype "passive"))
    )
    (net (code "94") (name "unconnected-(P5-Padc13)") (class "Default")
      (node (ref "P5") (pin "c13") (pinfunction "c13_c13") (pintype "passive"))
    )
    (net (code "95") (name "unconnected-(U12-R2OUT-Pad9)") (class "Default")
      (node (ref "U12") (pin "9") (pinfunction "R2OUT_9") (pintype "output"))
    )
    (net (code "96") (name "unconnected-(U12-T2OUT-Pad7)") (class "Default")
      (node (ref "U12") (pin "7") (pinfunction "T2OUT_7") (pintype "output"))
    )
    (net (code "97") (name "unconnected-(U13-HPLCOM-Pad20)") (class "Default")
      (node (ref "U13") (pin "20") (pinfunction "HPLCOM_20") (pintype "passive"))
    )
    (net (code "98") (name "unconnected-(U13-HPLOUT-Pad19)") (class "Default")
      (node (ref "U13") (pin "19") (pinfunction "HPLOUT_19") (pintype "passive"))
    )
    (net (code "99") (name "unconnected-(U13-LEFT_LOM-Pad28)") (class "Default")
      (node (ref "U13") (pin "28") (pinfunction "LEFT_LOM_28") (pintype "passive"))
    )
    (net (code "100") (name "unconnected-(U13-MIC2L-Pad14)") (class "Default")
      (node (ref "U13") (pin "14") (pinfunction "MIC2L_14") (pintype "passive"))
    )
    (net (code "101") (name "unconnected-(U13-MIC2R-Pad16)") (class "Default")
      (node (ref "U13") (pin "16") (pinfunction "MIC2R_16") (pintype "passive"))
    )
    (net (code "102") (name "unconnected-(U13-MICBIAS-Pad15)") (class "Default")
      (node (ref "U13") (pin "15") (pinfunction "MICBIAS_15") (pintype "passive"))
    )
    (net (code "103") (name "unconnected-(U13-RIGHT_LOM-Pad30)") (class "Default")
      (node (ref "U13") (pin "30") (pinfunction "RIGHT_LOM_30") (pintype "passive"))
    )
    (net (code "104") (name "unconnected-(U13-RIGHT_LOP-Pad29)") (class "Default")
      (node (ref "U13") (pin "29") (pinfunction "RIGHT_LOP_29") (pintype "passive"))
    )
  )
)
